# USB_power.net
KiCad netlist of a schematic drawn in Altium Designer
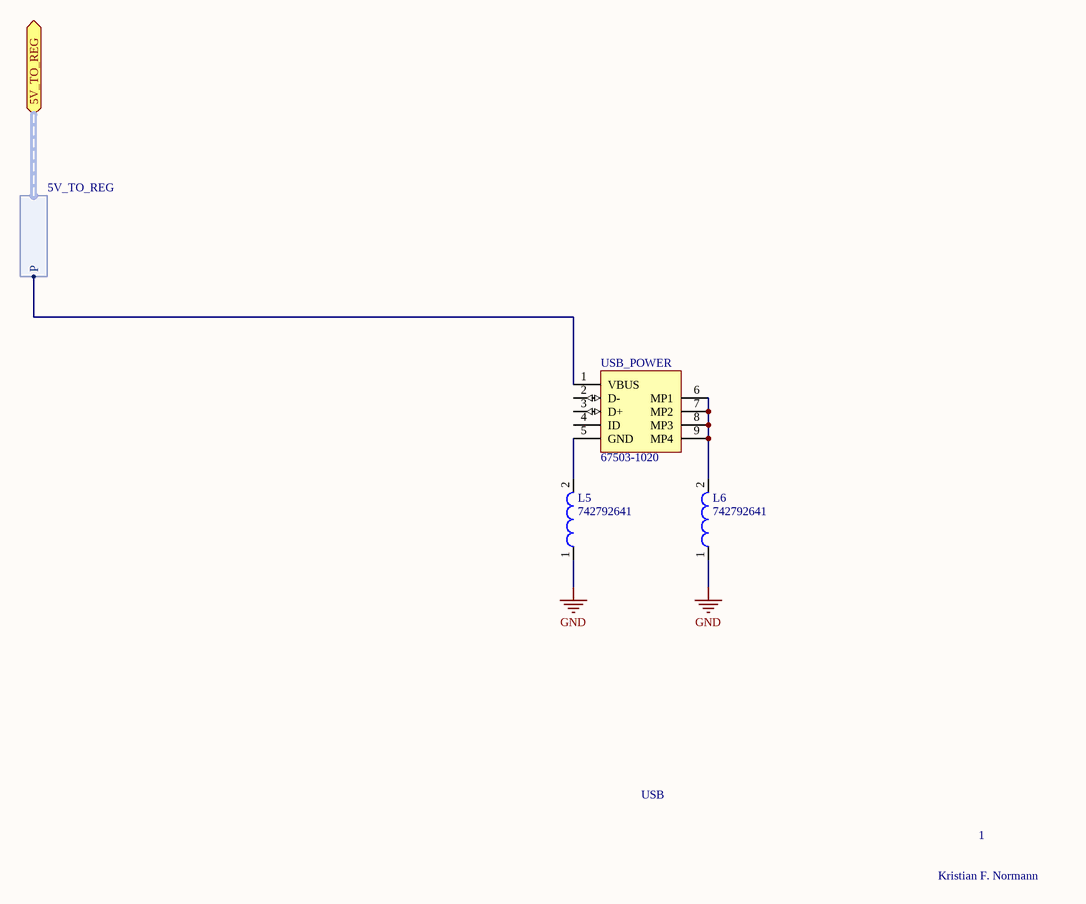
[diagram p0: USB_power.SchDoc]

(export (version "E")
  (design (tool "Eeschema 10.0.6"))
  (components
    (comp (ref "L5")
      (value "742792641")
      (footprint "SMD-0603")
      (description "SMD EMI Suppression Ferrite Bead WE-CBF, Z = 300 Ohm")
      (libsource (lib "Altium Content Vault") (part "PAS-IND-INDUCTOR-2"))
    )
    (comp (ref "L6")
      (value "742792641")
      (footprint "SMD-0603")
      (description "SMD EMI Suppression Ferrite Bead WE-CBF, Z = 300 Ohm")
      (libsource (lib "Altium Content Vault") (part "PAS-IND-INDUCTOR-2"))
    )
    (comp (ref "USB_POWER")
      (value "67503-1020")
      (footprint "MOLX-67503-1020_V")
      (description "USB, MINI, SMD, RA KME04-USBMU03A01")
      (fields (field (name "MANUFACTURER") "Molex"))
      (libsource (lib "Altium Content Vault") (part "CMP-0411-00002-1"))
    )
  )
  (nets
    (net (code "1") (name "/P") (class "Default")
      (node (ref "USB_POWER") (pin "1") (pinfunction "VBUS_1") (pintype "power_in"))
    )
    (net (code "2") (name "GND") (class "Default")
      (node (ref "L5") (pin "1") (pinfunction "1_1") (pintype "passive"))
      (node (ref "L6") (pin "1") (pinfunction "1_1") (pintype "passive"))
    )
    (net (code "3") (name "Net-(USB_POWER-GND)") (class "Default")
      (node (ref "L5") (pin "2") (pinfunction "2_2") (pintype "passive"))
      (node (ref "USB_POWER") (pin "5") (pinfunction "GND_5") (pintype "power_in"))
    )
    (net (code "4") (name "Net-(USB_POWER-MP1)") (class "Default")
      (node (ref "L6") (pin "2") (pinfunction "2_2") (pintype "passive"))
      (node (ref "USB_POWER") (pin "6") (pinfunction "MP1_6") (pintype "passive"))
      (node (ref "USB_POWER") (pin "7") (pinfunction "MP2_7") (pintype "passive"))
      (node (ref "USB_POWER") (pin "8") (pinfunction "MP3_8") (pintype "passive"))
      (node (ref "USB_POWER") (pin "9") (pinfunction "MP4_9") (pintype "passive"))
    )
    (net (code "5") (name "unconnected-(USB_POWER-D+-Pad3)") (class "Default")
      (node (ref "USB_POWER") (pin "3") (pinfunction "D+_3") (pintype "bidirectional"))
    )
    (net (code "6") (name "unconnected-(USB_POWER-D--Pad2)") (class "Default")
      (node (ref "USB_POWER") (pin "2") (pinfunction "D-_2") (pintype "bidirectional"))
    )
    (net (code "7") (name "unconnected-(USB_POWER-ID-Pad4)") (class "Default")
      (node (ref "USB_POWER") (pin "4") (pinfunction "ID_4") (pintype "passive"))
    )
  )
)
